# Pollin_NetIO_Clone.net
KiCad netlist of a schematic drawn in EAGLE
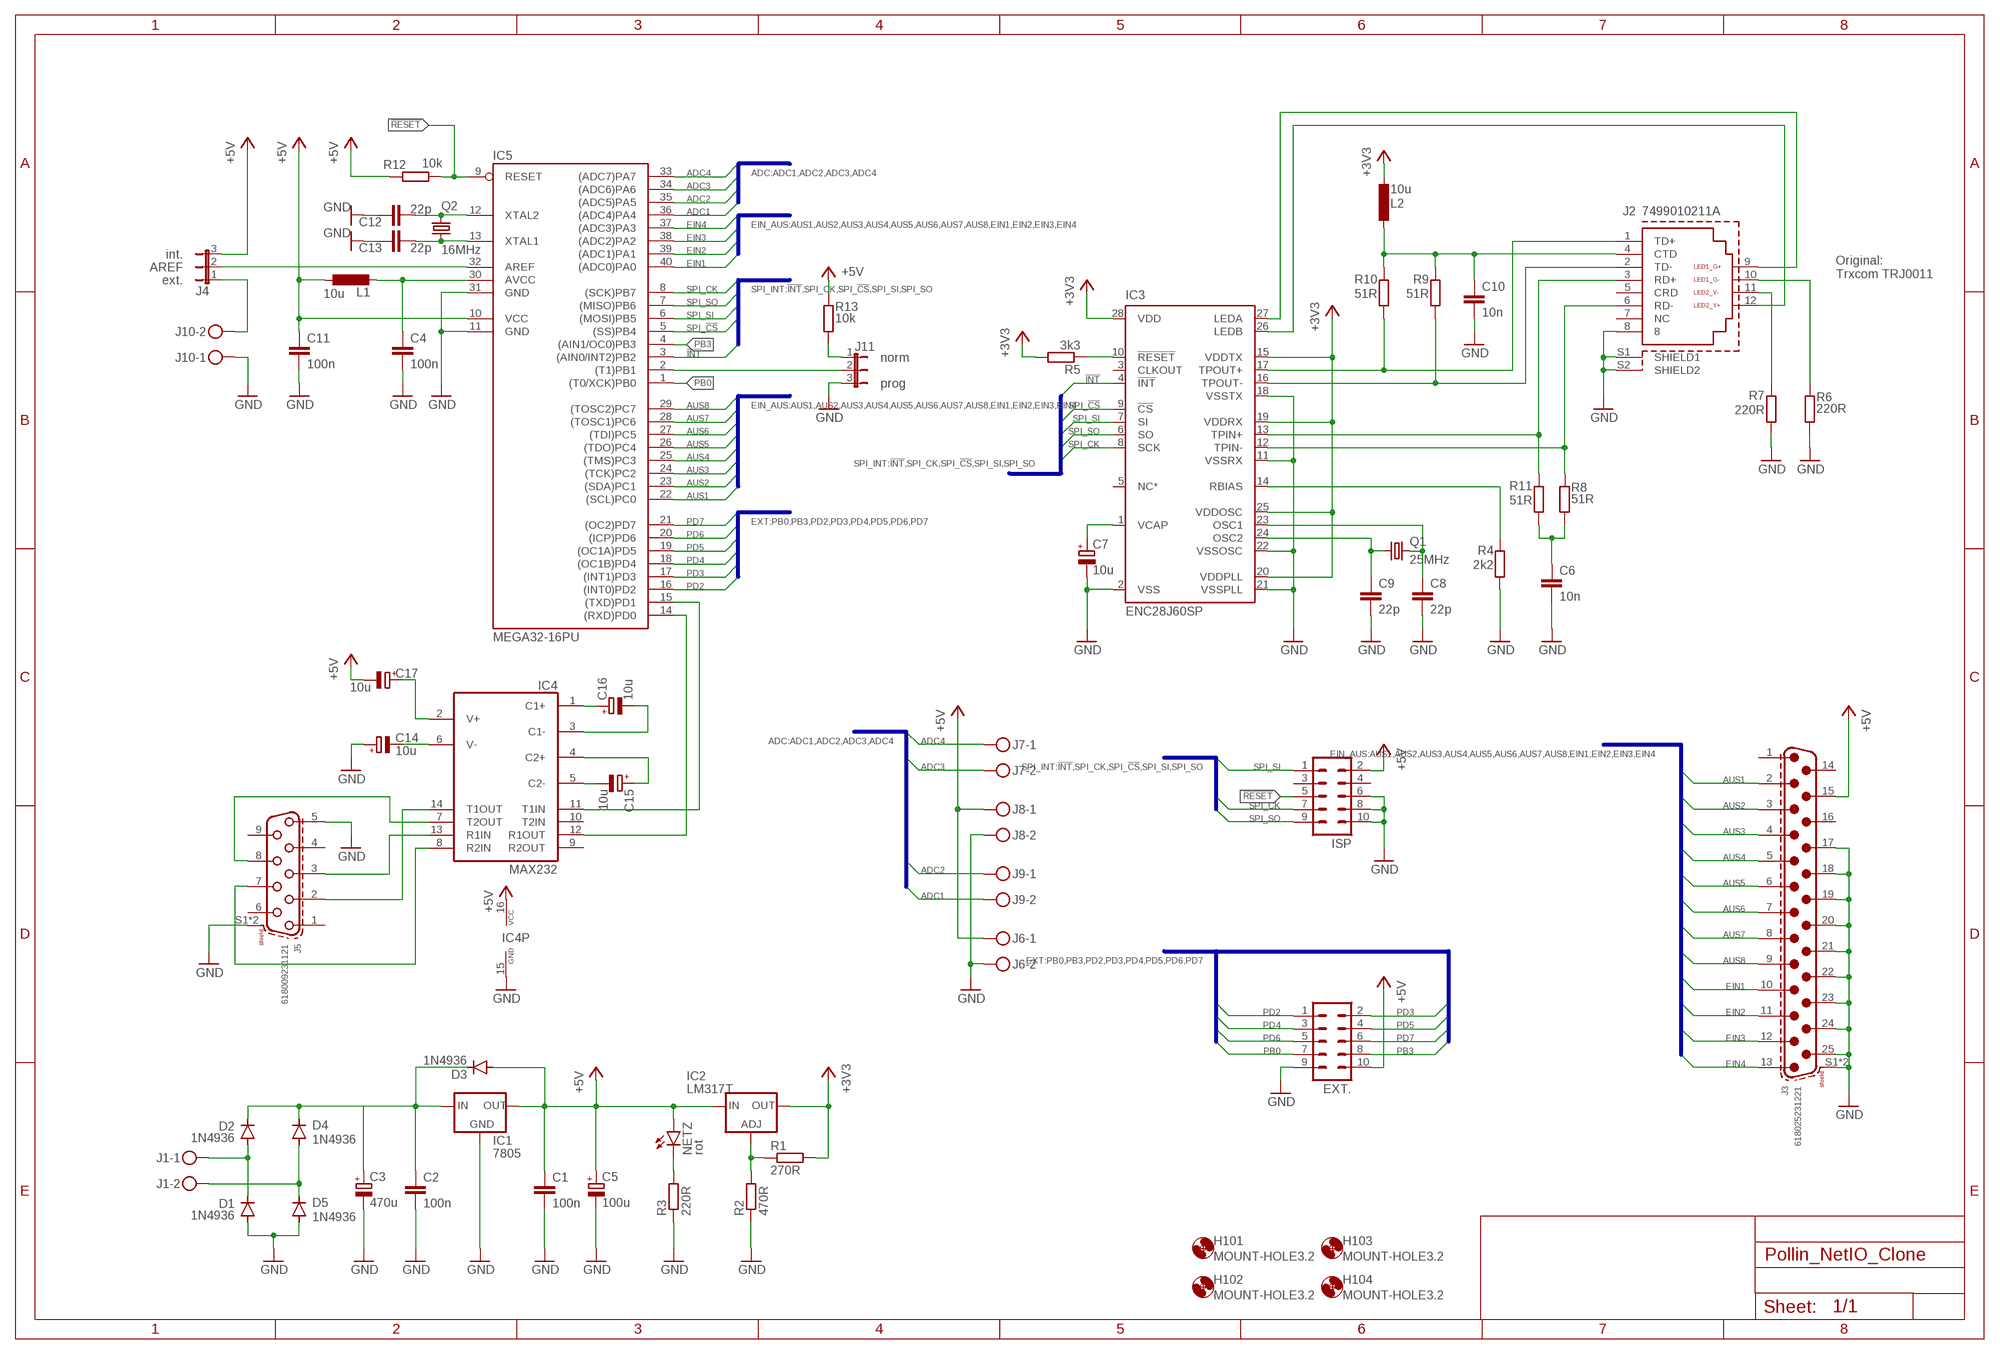
[diagram p0: schematic, sheet 1]

(export (version "E")
  (design (tool "Eeschema 10.0.6"))
  (components
    (comp (ref "C1")
      (value "100n")
      (footprint "eagle-import:C050-025X075")
      (libsource (lib "eagle-import") (part "C-EU050-025X075"))
    )
    (comp (ref "C2")
      (value "100n")
      (footprint "eagle-import:C050-025X075")
      (libsource (lib "eagle-import") (part "C-EU050-025X075"))
    )
    (comp (ref "C3")
      (value "470u")
      (footprint "eagle-import:E5-10,5")
      (libsource (lib "eagle-import") (part "CPOL-EUE5-10.5"))
    )
    (comp (ref "C4")
      (value "100n")
      (footprint "eagle-import:C050-025X075")
      (libsource (lib "eagle-import") (part "C-EU050-025X075"))
    )
    (comp (ref "C5")
      (value "100u")
      (footprint "eagle-import:E5-5")
      (libsource (lib "eagle-import") (part "CPOL-EUE5-5"))
    )
    (comp (ref "C6")
      (value "10n")
      (footprint "eagle-import:C050-025X075")
      (libsource (lib "eagle-import") (part "C-EU050-025X075"))
    )
    (comp (ref "C7")
      (value "10u")
      (footprint "eagle-import:E5-5")
      (libsource (lib "eagle-import") (part "CPOL-EUE5-5"))
    )
    (comp (ref "C8")
      (value "22p")
      (footprint "eagle-import:C050-024X044")
      (libsource (lib "eagle-import") (part "C-EU050-024X044"))
    )
    (comp (ref "C9")
      (value "22p")
      (footprint "eagle-import:C050-024X044")
      (libsource (lib "eagle-import") (part "C-EU050-024X044"))
    )
    (comp (ref "C10")
      (value "10n")
      (footprint "eagle-import:C050-025X075")
      (libsource (lib "eagle-import") (part "C-EU050-025X075"))
    )
    (comp (ref "C11")
      (value "100n")
      (footprint "eagle-import:C050-025X075")
      (libsource (lib "eagle-import") (part "C-EU050-025X075"))
    )
    (comp (ref "C12")
      (value "22p")
      (footprint "eagle-import:C050-024X044")
      (libsource (lib "eagle-import") (part "C-EU050-024X044"))
    )
    (comp (ref "C13")
      (value "22p")
      (footprint "eagle-import:C050-024X044")
      (libsource (lib "eagle-import") (part "C-EU050-024X044"))
    )
    (comp (ref "C14")
      (value "10u")
      (footprint "eagle-import:E5-5")
      (libsource (lib "eagle-import") (part "CPOL-EUE5-5"))
    )
    (comp (ref "C15")
      (value "10u")
      (footprint "eagle-import:E5-5")
      (libsource (lib "eagle-import") (part "CPOL-EUE5-5"))
    )
    (comp (ref "C16")
      (value "10u")
      (footprint "eagle-import:E5-5")
      (libsource (lib "eagle-import") (part "CPOL-EUE5-5"))
    )
    (comp (ref "C17")
      (value "10u")
      (footprint "eagle-import:E5-5")
      (libsource (lib "eagle-import") (part "CPOL-EUE5-5"))
    )
    (comp (ref "D1")
      (value "1N4936")
      (footprint "eagle-import:DO41-10")
      (libsource (lib "eagle-import") (part "1N4933"))
    )
    (comp (ref "D2")
      (value "1N4936")
      (footprint "eagle-import:DO41-10")
      (libsource (lib "eagle-import") (part "1N4933"))
    )
    (comp (ref "D3")
      (value "1N4936")
      (footprint "eagle-import:DO41-10")
      (libsource (lib "eagle-import") (part "1N4933"))
    )
    (comp (ref "D4")
      (value "1N4936")
      (footprint "eagle-import:DO41-10")
      (libsource (lib "eagle-import") (part "1N4933"))
    )
    (comp (ref "D5")
      (value "1N4936")
      (footprint "eagle-import:DO41-10")
      (libsource (lib "eagle-import") (part "1N4933"))
    )
    (comp (ref "EXT.")
      (value "ML10")
      (footprint "eagle-import:ML10")
      (libsource (lib "eagle-import") (part "ML10"))
    )
    (comp (ref "H101")
      (value "MOUNT-HOLE3.2")
      (footprint "eagle-import:3,2")
      (libsource (lib "eagle-import") (part "MOUNT-HOLE3.2"))
    )
    (comp (ref "H102")
      (value "MOUNT-HOLE3.2")
      (footprint "eagle-import:3,2")
      (libsource (lib "eagle-import") (part "MOUNT-HOLE3.2"))
    )
    (comp (ref "H103")
      (value "MOUNT-HOLE3.2")
      (footprint "eagle-import:3,2")
      (libsource (lib "eagle-import") (part "MOUNT-HOLE3.2"))
    )
    (comp (ref "H104")
      (value "MOUNT-HOLE3.2")
      (footprint "eagle-import:3,2")
      (libsource (lib "eagle-import") (part "MOUNT-HOLE3.2"))
    )
    (comp (ref "IC1")
      (value "7805")
      (footprint "eagle-import:78XXS")
      (libsource (lib "eagle-import") (part "78XXS"))
    )
    (comp (ref "IC2")
      (value "LM317T")
      (footprint "eagle-import:317TS")
      (libsource (lib "eagle-import") (part "LM317TS"))
    )
    (comp (ref "IC3")
      (value "ENC28J60SP")
      (footprint "eagle-import:DIL28-3")
      (fields (field (name "MF") "MICROCHIP") (field (name "MPN") "ENC28J60/SP"))
      (libsource (lib "eagle-import") (part "ENC28J60SP"))
    )
    (comp (ref "IC4")
      (value "MAX232")
      (footprint "eagle-import:DIL16")
      (fields (field (name "MF") "MAXIM") (field (name "MPN") "MAX232ACPE+"))
      (libsource (lib "eagle-import") (part "MAX232"))
    )
    (comp (ref "IC5")
      (value "MEGA32-16PU")
      (footprint "eagle-import:DIL40")
      (fields (field (name "MPN") "ATMEGA32-16PU"))
      (libsource (lib "eagle-import") (part "MEGA32-P"))
    )
    (comp (ref "ISP")
      (value "ML10")
      (footprint "eagle-import:ML10")
      (libsource (lib "eagle-import") (part "ML10"))
    )
    (comp (ref "J1")
      (value "MKDSN1,5/2-5,08")
      (footprint "eagle-import:MKDSN1,5_2-5,08")
      (libsource (lib "eagle-import") (part "MKDSN1,5/2-5,08"))
    )
    (comp (ref "J2")
      (value "7499010211A")
      (footprint "eagle-import:7499010211A")
      (libsource (lib "eagle-import") (part "WE-RJ45_7499010211A"))
    )
    (comp (ref "J3")
      (value "618025231221")
      (footprint "eagle-import:618025231221")
      (libsource (lib "eagle-import") (part "6180XX231221_618025231221"))
    )
    (comp (ref "J4")
      (value "JP2E")
      (footprint "eagle-import:JP2")
      (libsource (lib "eagle-import") (part "JP2E"))
    )
    (comp (ref "J5")
      (value "618009231121")
      (footprint "eagle-import:618009231121")
      (libsource (lib "eagle-import") (part "6180XX231121_618009231121"))
    )
    (comp (ref "J6")
      (value "MKDSN1,5/2-5,08")
      (footprint "eagle-import:MKDSN1,5_2-5,08")
      (libsource (lib "eagle-import") (part "MKDSN1,5/2-5,08"))
    )
    (comp (ref "J7")
      (value "MKDSN1,5/2-5,08")
      (footprint "eagle-import:MKDSN1,5_2-5,08")
      (libsource (lib "eagle-import") (part "MKDSN1,5/2-5,08"))
    )
    (comp (ref "J8")
      (value "MKDSN1,5/2-5,08")
      (footprint "eagle-import:MKDSN1,5_2-5,08")
      (libsource (lib "eagle-import") (part "MKDSN1,5/2-5,08"))
    )
    (comp (ref "J9")
      (value "MKDSN1,5/2-5,08")
      (footprint "eagle-import:MKDSN1,5_2-5,08")
      (libsource (lib "eagle-import") (part "MKDSN1,5/2-5,08"))
    )
    (comp (ref "J10")
      (value "MKDSN1,5/2-5,08")
      (footprint "eagle-import:MKDSN1,5_2-5,08")
      (libsource (lib "eagle-import") (part "MKDSN1,5/2-5,08"))
    )
    (comp (ref "J11")
      (value "JP2E")
      (footprint "eagle-import:JP2")
      (libsource (lib "eagle-import") (part "JP2E"))
    )
    (comp (ref "L1")
      (value "10u")
      (footprint "eagle-import:0207_15")
      (libsource (lib "eagle-import") (part "L-EU0207/15"))
    )
    (comp (ref "L2")
      (value "10u")
      (footprint "eagle-import:0207_15")
      (libsource (lib "eagle-import") (part "L-EU0207/15"))
    )
    (comp (ref "NETZ")
      (value "rot")
      (footprint "eagle-import:LED5MM")
      (libsource (lib "eagle-import") (part "LED5MM"))
    )
    (comp (ref "Q1")
      (value "25MHz")
      (footprint "eagle-import:HC49_S")
      (libsource (lib "eagle-import") (part "CRYSTALHC49S"))
    )
    (comp (ref "Q2")
      (value "16MHz")
      (footprint "eagle-import:HC49_S")
      (libsource (lib "eagle-import") (part "CRYSTALHC49S"))
    )
    (comp (ref "R1")
      (value "270R")
      (footprint "eagle-import:0207_10")
      (libsource (lib "eagle-import") (part "R-EU_0207/10"))
    )
    (comp (ref "R2")
      (value "470R")
      (footprint "eagle-import:0207_10")
      (libsource (lib "eagle-import") (part "R-EU_0207/10"))
    )
    (comp (ref "R3")
      (value "220R")
      (footprint "eagle-import:0207_10")
      (libsource (lib "eagle-import") (part "R-EU_0207/10"))
    )
    (comp (ref "R4")
      (value "2k2")
      (footprint "eagle-import:0207_10")
      (libsource (lib "eagle-import") (part "R-EU_0207/10"))
    )
    (comp (ref "R5")
      (value "3k3")
      (footprint "eagle-import:0207_10")
      (libsource (lib "eagle-import") (part "R-EU_0207/10"))
    )
    (comp (ref "R6")
      (value "220R")
      (footprint "eagle-import:0207_10")
      (libsource (lib "eagle-import") (part "R-EU_0207/10"))
    )
    (comp (ref "R7")
      (value "220R")
      (footprint "eagle-import:0207_10")
      (libsource (lib "eagle-import") (part "R-EU_0207/10"))
    )
    (comp (ref "R8")
      (value "51R")
      (footprint "eagle-import:0207_10")
      (libsource (lib "eagle-import") (part "R-EU_0207/10"))
    )
    (comp (ref "R9")
      (value "51R")
      (footprint "eagle-import:0207_10")
      (libsource (lib "eagle-import") (part "R-EU_0207/10"))
    )
    (comp (ref "R10")
      (value "51R")
      (footprint "eagle-import:0207_10")
      (libsource (lib "eagle-import") (part "R-EU_0207/10"))
    )
    (comp (ref "R11")
      (value "51R")
      (footprint "eagle-import:0207_10")
      (libsource (lib "eagle-import") (part "R-EU_0207/10"))
    )
    (comp (ref "R12")
      (value "10k")
      (footprint "eagle-import:0207_10")
      (libsource (lib "eagle-import") (part "R-EU_0207/10"))
    )
    (comp (ref "R13")
      (value "10k")
      (footprint "eagle-import:0207_10")
      (libsource (lib "eagle-import") (part "R-EU_0207/10"))
    )
  )
  (nets
    (net (code "5") (name "+3V3") (class "Default")
      (node (ref "IC2") (pin "2") (pinfunction "OUT_2") (pintype "passive"))
      (node (ref "IC3") (pin "15") (pinfunction "VDDTX_15") (pintype "input"))
      (node (ref "IC3") (pin "19") (pinfunction "VDDRX_19") (pintype "input"))
      (node (ref "IC3") (pin "20") (pinfunction "VDDPLL_20") (pintype "input"))
      (node (ref "IC3") (pin "25") (pinfunction "VDDOSC_25") (pintype "input"))
      (node (ref "IC3") (pin "28") (pinfunction "VDD_28") (pintype "input"))
      (node (ref "L2") (pin "2") (pinfunction "2_2") (pintype "passive"))
      (node (ref "R1") (pin "2") (pinfunction "2_2") (pintype "passive"))
      (node (ref "R5") (pin "2") (pinfunction "2_2") (pintype "passive"))
    )
    (net (code "6") (name "+5V") (class "Default")
      (node (ref "C1") (pin "1") (pinfunction "1_1") (pintype "passive"))
      (node (ref "C11") (pin "1") (pinfunction "1_1") (pintype "passive"))
      (node (ref "C17") (pin "-") (pinfunction "-_-") (pintype "passive"))
      (node (ref "C5") (pin "+") (pinfunction "+_+") (pintype "passive"))
      (node (ref "D3") (pin "A") (pinfunction "A_A") (pintype "passive"))
      (node (ref "EXT.") (pin "10") (pinfunction "10_10") (pintype "passive"))
      (node (ref "IC1") (pin "OUT") (pinfunction "OUT_OUT") (pintype "passive"))
      (node (ref "IC2") (pin "3") (pinfunction "IN_3") (pintype "input"))
      (node (ref "IC4") (pin "16") (pinfunction "VCC_16") (pintype "power_in"))
      (node (ref "IC5") (pin "10") (pinfunction "VCC_10") (pintype "power_in"))
      (node (ref "ISP") (pin "2") (pinfunction "2_2") (pintype "passive"))
      (node (ref "J3") (pin "15") (pinfunction "15_15") (pintype "bidirectional"))
      (node (ref "J4") (pin "3") (pinfunction "3_3") (pintype "passive"))
      (node (ref "J6") (pin "1") (pinfunction "KL_1") (pintype "passive"))
      (node (ref "J8") (pin "1") (pinfunction "KL_1") (pintype "passive"))
      (node (ref "L1") (pin "1") (pinfunction "1_1") (pintype "passive"))
      (node (ref "NETZ") (pin "A") (pinfunction "A_A") (pintype "passive"))
      (node (ref "R12") (pin "1") (pinfunction "1_1") (pintype "passive"))
      (node (ref "R13") (pin "2") (pinfunction "2_2") (pintype "passive"))
    )
    (net (code "7") (name "/ADC1") (class "Default")
      (node (ref "IC5") (pin "36") (pinfunction "(ADC4)PA4_36") (pintype "bidirectional"))
      (node (ref "J9") (pin "2") (pinfunction "KL_2") (pintype "passive"))
    )
    (net (code "8") (name "/ADC2") (class "Default")
      (node (ref "IC5") (pin "35") (pinfunction "(ADC5)PA5_35") (pintype "bidirectional"))
      (node (ref "J9") (pin "1") (pinfunction "KL_1") (pintype "passive"))
    )
    (net (code "9") (name "/ADC3") (class "Default")
      (node (ref "IC5") (pin "34") (pinfunction "(ADC6)PA6_34") (pintype "bidirectional"))
      (node (ref "J7") (pin "2") (pinfunction "KL_2") (pintype "passive"))
    )
    (net (code "10") (name "/ADC4") (class "Default")
      (node (ref "IC5") (pin "33") (pinfunction "(ADC7)PA7_33") (pintype "bidirectional"))
      (node (ref "J7") (pin "1") (pinfunction "KL_1") (pintype "passive"))
    )
    (net (code "11") (name "/AUS1") (class "Default")
      (node (ref "IC5") (pin "22") (pinfunction "(SCL)PC0_22") (pintype "bidirectional"))
      (node (ref "J3") (pin "2") (pinfunction "2_2") (pintype "bidirectional"))
    )
    (net (code "12") (name "/AUS2") (class "Default")
      (node (ref "IC5") (pin "23") (pinfunction "(SDA)PC1_23") (pintype "bidirectional"))
      (node (ref "J3") (pin "3") (pinfunction "3_3") (pintype "bidirectional"))
    )
    (net (code "13") (name "/AUS3") (class "Default")
      (node (ref "IC5") (pin "24") (pinfunction "(TCK)PC2_24") (pintype "bidirectional"))
      (node (ref "J3") (pin "4") (pinfunction "4_4") (pintype "bidirectional"))
    )
    (net (code "14") (name "/AUS4") (class "Default")
      (node (ref "IC5") (pin "25") (pinfunction "(TMS)PC3_25") (pintype "bidirectional"))
      (node (ref "J3") (pin "5") (pinfunction "5_5") (pintype "bidirectional"))
    )
    (net (code "15") (name "/AUS5") (class "Default")
      (node (ref "IC5") (pin "26") (pinfunction "(TDO)PC4_26") (pintype "bidirectional"))
      (node (ref "J3") (pin "6") (pinfunction "6_6") (pintype "bidirectional"))
    )
    (net (code "16") (name "/AUS6") (class "Default")
      (node (ref "IC5") (pin "27") (pinfunction "(TDI)PC5_27") (pintype "bidirectional"))
      (node (ref "J3") (pin "7") (pinfunction "7_7") (pintype "bidirectional"))
    )
    (net (code "17") (name "/AUS7") (class "Default")
      (node (ref "IC5") (pin "28") (pinfunction "(TOSC1)PC6_28") (pintype "bidirectional"))
      (node (ref "J3") (pin "8") (pinfunction "8_8") (pintype "bidirectional"))
    )
    (net (code "18") (name "/AUS8") (class "Default")
      (node (ref "IC5") (pin "29") (pinfunction "(TOSC2)PC7_29") (pintype "bidirectional"))
      (node (ref "J3") (pin "9") (pinfunction "9_9") (pintype "bidirectional"))
    )
    (net (code "19") (name "/EIN1") (class "Default")
      (node (ref "IC5") (pin "40") (pinfunction "(ADC0)PA0_40") (pintype "bidirectional"))
      (node (ref "J3") (pin "10") (pinfunction "10_10") (pintype "bidirectional"))
    )
    (net (code "20") (name "/EIN2") (class "Default")
      (node (ref "IC5") (pin "39") (pinfunction "(ADC1)PA1_39") (pintype "bidirectional"))
      (node (ref "J3") (pin "11") (pinfunction "11_11") (pintype "bidirectional"))
    )
    (net (code "21") (name "/EIN3") (class "Default")
      (node (ref "IC5") (pin "38") (pinfunction "(ADC2)PA2_38") (pintype "bidirectional"))
      (node (ref "J3") (pin "12") (pinfunction "12_12") (pintype "bidirectional"))
    )
    (net (code "22") (name "/EIN4") (class "Default")
      (node (ref "IC5") (pin "37") (pinfunction "(ADC3)PA3_37") (pintype "bidirectional"))
      (node (ref "J3") (pin "13") (pinfunction "13_13") (pintype "bidirectional"))
    )
    (net (code "23") (name "/PD2") (class "Default")
      (node (ref "EXT.") (pin "1") (pinfunction "1_1") (pintype "passive"))
      (node (ref "IC5") (pin "16") (pinfunction "(INT0)PD2_16") (pintype "bidirectional"))
    )
    (net (code "24") (name "/PD3") (class "Default")
      (node (ref "EXT.") (pin "2") (pinfunction "2_2") (pintype "passive"))
      (node (ref "IC5") (pin "17") (pinfunction "(INT1)PD3_17") (pintype "bidirectional"))
    )
    (net (code "25") (name "/PD4") (class "Default")
      (node (ref "EXT.") (pin "3") (pinfunction "3_3") (pintype "passive"))
      (node (ref "IC5") (pin "18") (pinfunction "(OC1B)PD4_18") (pintype "bidirectional"))
    )
    (net (code "26") (name "/PD5") (class "Default")
      (node (ref "EXT.") (pin "4") (pinfunction "4_4") (pintype "passive"))
      (node (ref "IC5") (pin "19") (pinfunction "(OC1A)PD5_19") (pintype "bidirectional"))
    )
    (net (code "27") (name "/PD6") (class "Default")
      (node (ref "EXT.") (pin "5") (pinfunction "5_5") (pintype "passive"))
      (node (ref "IC5") (pin "20") (pinfunction "(ICP)PD6_20") (pintype "bidirectional"))
    )
    (net (code "28") (name "/PD7") (class "Default")
      (node (ref "EXT.") (pin "6") (pinfunction "6_6") (pintype "passive"))
      (node (ref "IC5") (pin "21") (pinfunction "(OC2)PD7_21") (pintype "bidirectional"))
    )
    (net (code "29") (name "/SPI_CK") (class "Default")
      (node (ref "IC3") (pin "8") (pinfunction "SCK_8") (pintype "input"))
      (node (ref "IC5") (pin "8") (pinfunction "(SCK)PB7_8") (pintype "bidirectional"))
      (node (ref "ISP") (pin "7") (pinfunction "7_7") (pintype "passive"))
    )
    (net (code "30") (name "/SPI_SI") (class "Default")
      (node (ref "IC3") (pin "7") (pinfunction "SI_7") (pintype "input"))
      (node (ref "IC5") (pin "6") (pinfunction "(MOSI)PB5_6") (pintype "bidirectional"))
      (node (ref "ISP") (pin "1") (pinfunction "1_1") (pintype "passive"))
    )
    (net (code "31") (name "/SPI_SO") (class "Default")
      (node (ref "IC3") (pin "6") (pinfunction "SO_6") (pintype "output"))
      (node (ref "IC5") (pin "7") (pinfunction "(MISO)PB6_7") (pintype "bidirectional"))
      (node (ref "ISP") (pin "9") (pinfunction "9_9") (pintype "passive"))
    )
    (net (code "32") (name "/SPI_~{CS}") (class "Default")
      (node (ref "IC3") (pin "9") (pinfunction "~{CS}_9") (pintype "input"))
      (node (ref "IC5") (pin "5") (pinfunction "(SS)PB4_5") (pintype "bidirectional"))
    )
    (net (code "37") (name "/~{INT}") (class "Default")
      (node (ref "IC3") (pin "4") (pinfunction "~{INT}_4") (pintype "output"))
      (node (ref "IC5") (pin "3") (pinfunction "(AIN0/INT2)PB2_3") (pintype "bidirectional"))
    )
    (net (code "38") (name "/~{RESET}") (class "Default")
      (node (ref "IC5") (pin "9") (pinfunction "RESET_9") (pintype "input"))
      (node (ref "ISP") (pin "5") (pinfunction "5_5") (pintype "passive"))
      (node (ref "R12") (pin "2") (pinfunction "2_2") (pintype "passive"))
    )
    (net (code "39") (name "GND") (class "Default")
      (node (ref "C1") (pin "2") (pinfunction "2_2") (pintype "passive"))
      (node (ref "C10") (pin "2") (pinfunction "2_2") (pintype "passive"))
      (node (ref "C11") (pin "2") (pinfunction "2_2") (pintype "passive"))
      (node (ref "C12") (pin "1") (pinfunction "1_1") (pintype "passive"))
      (node (ref "C13") (pin "1") (pinfunction "1_1") (pintype "passive"))
      (node (ref "C14") (pin "+") (pinfunction "+_+") (pintype "passive"))
      (node (ref "C2") (pin "2") (pinfunction "2_2") (pintype "passive"))
      (node (ref "C3") (pin "-") (pinfunction "-_-") (pintype "passive"))
      (node (ref "C4") (pin "2") (pinfunction "2_2") (pintype "passive"))
      (node (ref "C5") (pin "-") (pinfunction "-_-") (pintype "passive"))
      (node (ref "C6") (pin "2") (pinfunction "2_2") (pintype "passive"))
      (node (ref "C7") (pin "-") (pinfunction "-_-") (pintype "passive"))
      (node (ref "C8") (pin "2") (pinfunction "2_2") (pintype "passive"))
      (node (ref "C9") (pin "2") (pinfunction "2_2") (pintype "passive"))
      (node (ref "D1") (pin "A") (pinfunction "A_A") (pintype "passive"))
      (node (ref "D5") (pin "A") (pinfunction "A_A") (pintype "passive"))
      (node (ref "EXT.") (pin "9") (pinfunction "9_9") (pintype "passive"))
      (node (ref "IC1") (pin "GND") (pinfunction "GND_GND") (pintype "input"))
      (node (ref "IC3") (pin "11") (pinfunction "VSSRX_11") (pintype "input"))
      (node (ref "IC3") (pin "18") (pinfunction "VSSTX_18") (pintype "input"))
      (node (ref "IC3") (pin "2") (pinfunction "VSS_2") (pintype "input"))
      (node (ref "IC3") (pin "21") (pinfunction "VSSPLL_21") (pintype "input"))
      (node (ref "IC3") (pin "22") (pinfunction "VSSOSC_22") (pintype "input"))
      (node (ref "IC4") (pin "15") (pinfunction "GND_15") (pintype "power_in"))
      (node (ref "IC5") (pin "11") (pinfunction "GND_11") (pintype "power_in"))
      (node (ref "IC5") (pin "31") (pinfunction "GND_31") (pintype "power_in"))
      (node (ref "ISP") (pin "10") (pinfunction "10_10") (pintype "passive"))
      (node (ref "ISP") (pin "6") (pinfunction "6_6") (pintype "passive"))
      (node (ref "ISP") (pin "8") (pinfunction "8_8") (pintype "passive"))
      (node (ref "J10") (pin "1") (pinfunction "KL_1") (pintype "passive"))
      (node (ref "J11") (pin "3") (pinfunction "3_3") (pintype "passive"))
      (node (ref "J2") (pin "8") (pinfunction "8_8") (pintype "passive"))
      (node (ref "J2") (pin "S1") (pinfunction "SHIELD1_S1") (pintype "passive"))
      (node (ref "J2") (pin "S2") (pinfunction "SHIELD2_S2") (pintype "passive"))
      (node (ref "J3") (pin "17") (pinfunction "17_17") (pintype "bidirectional"))
      (node (ref "J3") (pin "18") (pinfunction "18_18") (pintype "bidirectional"))
      (node (ref "J3") (pin "19") (pinfunction "19_19") (pintype "bidirectional"))
      (node (ref "J3") (pin "20") (pinfunction "20_20") (pintype "bidirectional"))
      (node (ref "J3") (pin "21") (pinfunction "21_21") (pintype "bidirectional"))
      (node (ref "J3") (pin "22") (pinfunction "22_22") (pintype "bidirectional"))
      (node (ref "J3") (pin "23") (pinfunction "23_23") (pintype "bidirectional"))
      (node (ref "J3") (pin "24") (pinfunction "24_24") (pintype "bidirectional"))
      (node (ref "J3") (pin "25") (pinfunction "25_25") (pintype "bidirectional"))
      (node (ref "J3") (pin "S1") (pinfunction "SHIELD_S1") (pintype "bidirectional"))
      (node (ref "J3") (pin "S2") (pinfunction "SHIELD_S2") (pintype "bidirectional"))
      (node (ref "J5") (pin "5") (pinfunction "5_5") (pintype "bidirectional"))
      (node (ref "J5") (pin "S1") (pinfunction "SHIELD_S1") (pintype "bidirectional"))
      (node (ref "J5") (pin "S2") (pinfunction "SHIELD_S2") (pintype "bidirectional"))
      (node (ref "J6") (pin "2") (pinfunction "KL_2") (pintype "passive"))
      (node (ref "J8") (pin "2") (pinfunction "KL_2") (pintype "passive"))
      (node (ref "R2") (pin "1") (pinfunction "1_1") (pintype "passive"))
      (node (ref "R3") (pin "1") (pinfunction "1_1") (pintype "passive"))
      (node (ref "R4") (pin "1") (pinfunction "1_1") (pintype "passive"))
      (node (ref "R6") (pin "1") (pinfunction "1_1") (pintype "passive"))
      (node (ref "R7") (pin "1") (pinfunction "1_1") (pintype "passive"))
    )
    (net (code "40") (name "Net-(C2-Pad1)") (class "Default")
      (node (ref "C2") (pin "1") (pinfunction "1_1") (pintype "passive"))
      (node (ref "C3") (pin "+") (pinfunction "+_+") (pintype "passive"))
      (node (ref "D2") (pin "C") (pinfunction "C_C") (pintype "passive"))
      (node (ref "D3") (pin "C") (pinfunction "C_C") (pintype "passive"))
      (node (ref "D4") (pin "C") (pinfunction "C_C") (pintype "passive"))
      (node (ref "IC1") (pin "IN") (pinfunction "IN_IN") (pintype "input"))
    )
    (net (code "41") (name "Net-(C6-Pad1)") (class "Default")
      (node (ref "C6") (pin "1") (pinfunction "1_1") (pintype "passive"))
      (node (ref "R11") (pin "1") (pinfunction "1_1") (pintype "passive"))
      (node (ref "R8") (pin "1") (pinfunction "1_1") (pintype "passive"))
    )
    (net (code "42") (name "Net-(IC2-ADJ)") (class "Default")
      (node (ref "IC2") (pin "1") (pinfunction "ADJ_1") (pintype "input"))
      (node (ref "R1") (pin "1") (pinfunction "1_1") (pintype "passive"))
      (node (ref "R2") (pin "2") (pinfunction "2_2") (pintype "passive"))
    )
    (net (code "43") (name "Net-(IC3-LEDA)") (class "Default")
      (node (ref "IC3") (pin "27") (pinfunction "LEDA_27") (pintype "output"))
      (node (ref "J2") (pin "9") (pinfunction "LED1_G+_9") (pintype "passive"))
    )
    (net (code "44") (name "Net-(IC3-LEDB)") (class "Default")
      (node (ref "IC3") (pin "26") (pinfunction "LEDB_26") (pintype "output"))
      (node (ref "J2") (pin "12") (pinfunction "LED2_Y+_12") (pintype "passive"))
    )
    (net (code "45") (name "Net-(IC3-OSC1)") (class "Default")
      (node (ref "C8") (pin "1") (pinfunction "1_1") (pintype "passive"))
      (node (ref "IC3") (pin "23") (pinfunction "OSC1_23") (pintype "input"))
      (node (ref "Q1") (pin "1") (pinfunction "1_1") (pintype "passive"))
    )
    (net (code "46") (name "Net-(IC3-OSC2)") (class "Default")
      (node (ref "C9") (pin "1") (pinfunction "1_1") (pintype "passive"))
      (node (ref "IC3") (pin "24") (pinfunction "OSC2_24") (pintype "output"))
      (node (ref "Q1") (pin "2") (pinfunction "2_2") (pintype "passive"))
    )
    (net (code "47") (name "Net-(IC3-RBIAS)") (class "Default")
      (node (ref "IC3") (pin "14") (pinfunction "RBIAS_14") (pintype "input"))
      (node (ref "R4") (pin "2") (pinfunction "2_2") (pintype "passive"))
    )
    (net (code "48") (name "Net-(IC3-TPIN+)") (class "Default")
      (node (ref "IC3") (pin "13") (pinfunction "TPIN+_13") (pintype "input"))
      (node (ref "J2") (pin "3") (pinfunction "RD+_3") (pintype "passive"))
      (node (ref "R11") (pin "2") (pinfunction "2_2") (pintype "passive"))
    )
    (net (code "49") (name "Net-(IC3-TPIN-)") (class "Default")
      (node (ref "IC3") (pin "12") (pinfunction "TPIN-_12") (pintype "input"))
      (node (ref "J2") (pin "6") (pinfunction "RD-_6") (pintype "passive"))
      (node (ref "R8") (pin "2") (pinfunction "2_2") (pintype "passive"))
    )
    (net (code "50") (name "Net-(IC3-TPOUT+)") (class "Default")
      (node (ref "IC3") (pin "17") (pinfunction "TPOUT+_17") (pintype "output"))
      (node (ref "J2") (pin "1") (pinfunction "TD+_1") (pintype "passive"))
      (node (ref "R10") (pin "1") (pinfunction "1_1") (pintype "passive"))
    )
    (net (code "51") (name "Net-(IC3-TPOUT-)") (class "Default")
      (node (ref "IC3") (pin "16") (pinfunction "TPOUT-_16") (pintype "output"))
      (node (ref "J2") (pin "2") (pinfunction "TD-_2") (pintype "passive"))
      (node (ref "R9") (pin "1") (pinfunction "1_1") (pintype "passive"))
    )
    (net (code "52") (name "Net-(IC3-VCAP)") (class "Default")
      (node (ref "C7") (pin "+") (pinfunction "+_+") (pintype "passive"))
      (node (ref "IC3") (pin "1") (pinfunction "VCAP_1") (pintype "input"))
    )
    (net (code "53") (name "Net-(IC3-~{RESET})") (class "Default")
      (node (ref "IC3") (pin "10") (pinfunction "~{RESET}_10") (pintype "input"))
      (node (ref "R5") (pin "1") (pinfunction "1_1") (pintype "passive"))
    )
    (net (code "54") (name "Net-(IC4A-C1+)") (class "Default")
      (node (ref "C16") (pin "+") (pinfunction "+_+") (pintype "passive"))
      (node (ref "IC4") (pin "1") (pinfunction "C1+_1") (pintype "bidirectional"))
    )
    (net (code "55") (name "Net-(IC4A-C1-)") (class "Default")
      (node (ref "C16") (pin "-") (pinfunction "-_-") (pintype "passive"))
      (node (ref "IC4") (pin "3") (pinfunction "C1-_3") (pintype "bidirectional"))
    )
    (net (code "56") (name "Net-(IC4A-C2+)") (class "Default")
      (node (ref "C15") (pin "+") (pinfunction "+_+") (pintype "passive"))
      (node (ref "IC4") (pin "4") (pinfunction "C2+_4") (pintype "bidirectional"))
    )
    (net (code "57") (name "Net-(IC4A-C2-)") (class "Default")
      (node (ref "C15") (pin "-") (pinfunction "-_-") (pintype "passive"))
      (node (ref "IC4") (pin "5") (pinfunction "C2-_5") (pintype "bidirectional"))
    )
    (net (code "58") (name "Net-(IC4A-R1IN)") (class "Default")
      (node (ref "IC4") (pin "13") (pinfunction "R1IN_13") (pintype "input"))
      (node (ref "J5") (pin "3") (pinfunction "3_3") (pintype "bidirectional"))
    )
    (net (code "59") (name "Net-(IC4A-R1OUT)") (class "Default")
      (node (ref "IC4") (pin "12") (pinfunction "R1OUT_12") (pintype "output"))
      (node (ref "IC5") (pin "14") (pinfunction "(RXD)PD0_14") (pintype "bidirectional"))
    )
    (net (code "60") (name "Net-(IC4A-R2IN)") (class "Default")
      (node (ref "IC4") (pin "8") (pinfunction "R2IN_8") (pintype "input"))
      (node (ref "J5") (pin "7") (pinfunction "7_7") (pintype "bidirectional"))
    )
    (net (code "61") (name "Net-(IC4A-T1IN)") (class "Default")
      (node (ref "IC4") (pin "11") (pinfunction "T1IN_11") (pintype "input"))
      (node (ref "IC5") (pin "15") (pinfunction "(TXD)PD1_15") (pintype "bidirectional"))
    )
    (net (code "62") (name "Net-(IC4A-T1OUT)") (class "Default")
      (node (ref "IC4") (pin "14") (pinfunction "T1OUT_14") (pintype "output"))
      (node (ref "J5") (pin "2") (pinfunction "2_2") (pintype "bidirectional"))
    )
    (net (code "63") (name "Net-(IC4A-T2OUT)") (class "Default")
      (node (ref "IC4") (pin "7") (pinfunction "T2OUT_7") (pintype "output"))
      (node (ref "J5") (pin "8") (pinfunction "8_8") (pintype "bidirectional"))
    )
    (net (code "64") (name "Net-(IC4A-V+)") (class "Default")
      (node (ref "C17") (pin "+") (pinfunction "+_+") (pintype "passive"))
      (node (ref "IC4") (pin "2") (pinfunction "V+_2") (pintype "bidirectional"))
    )
    (net (code "65") (name "Net-(IC4A-V-)") (class "Default")
      (node (ref "C14") (pin "-") (pinfunction "-_-") (pintype "passive"))
      (node (ref "IC4") (pin "6") (pinfunction "V-_6") (pintype "bidirectional"))
    )
    (net (code "66") (name "Net-(IC5-(T1)PB1)") (class "Default")
      (node (ref "IC5") (pin "2") (pinfunction "(T1)PB1_2") (pintype "bidirectional"))
      (node (ref "J11") (pin "2") (pinfunction "2_2") (pintype "passive"))
    )
    (net (code "67") (name "Net-(IC5-AREF)") (class "Default")
      (node (ref "IC5") (pin "32") (pinfunction "AREF_32") (pintype "passive"))
      (node (ref "J4") (pin "2") (pinfunction "2_2") (pintype "passive"))
    )
    (net (code "68") (name "Net-(IC5-AVCC)") (class "Default")
      (node (ref "C4") (pin "1") (pinfunction "1_1") (pintype "passive"))
      (node (ref "IC5") (pin "30") (pinfunction "AVCC_30") (pintype "power_in"))
      (node (ref "L1") (pin "2") (pinfunction "2_2") (pintype "passive"))
    )
    (net (code "69") (name "Net-(IC5-XTAL1)") (class "Default")
      (node (ref "C13") (pin "2") (pinfunction "2_2") (pintype "passive"))
      (node (ref "IC5") (pin "13") (pinfunction "XTAL1_13") (pintype "bidirectional"))
      (node (ref "Q2") (pin "1") (pinfunction "1_1") (pintype "passive"))
    )
    (net (code "70") (name "Net-(IC5-XTAL2)") (class "Default")
      (node (ref "C12") (pin "2") (pinfunction "2_2") (pintype "passive"))
      (node (ref "IC5") (pin "12") (pinfunction "XTAL2_12") (pintype "bidirectional"))
      (node (ref "Q2") (pin "2") (pinfunction "2_2") (pintype "passive"))
    )
    (net (code "71") (name "Net-(J1A-KL)") (class "Default")
      (node (ref "D1") (pin "C") (pinfunction "C_C") (pintype "passive"))
      (node (ref "D2") (pin "A") (pinfunction "A_A") (pintype "passive"))
      (node (ref "J1") (pin "1") (pinfunction "KL_1") (pintype "passive"))
    )
    (net (code "72") (name "Net-(J1B-KL)") (class "Default")
      (node (ref "D4") (pin "A") (pinfunction "A_A") (pintype "passive"))
      (node (ref "D5") (pin "C") (pinfunction "C_C") (pintype "passive"))
      (node (ref "J1") (pin "2") (pinfunction "KL_2") (pintype "passive"))
    )
    (net (code "73") (name "Net-(J2-CTD)") (class "Default")
      (node (ref "C10") (pin "1") (pinfunction "1_1") (pintype "passive"))
      (node (ref "J2") (pin "4") (pinfunction "CTD_4") (pintype "passive"))
      (node (ref "L2") (pin "1") (pinfunction "1_1") (pintype "passive"))
      (node (ref "R10") (pin "2") (pinfunction "2_2") (pintype "passive"))
      (node (ref "R9") (pin "2") (pinfunction "2_2") (pintype "passive"))
    )
    (net (code "74") (name "Net-(J2-LED1_G-)") (class "Default")
      (node (ref "J2") (pin "10") (pinfunction "LED1_G-_10") (pintype "passive"))
      (node (ref "R6") (pin "2") (pinfunction "2_2") (pintype "passive"))
    )
    (net (code "75") (name "Net-(J2-LED2_Y-)") (class "Default")
      (node (ref "J2") (pin "11") (pinfunction "LED2_Y-_11") (pintype "passive"))
      (node (ref "R7") (pin "2") (pinfunction "2_2") (pintype "passive"))
    )
    (net (code "76") (name "Net-(J10B-KL)") (class "Default")
      (node (ref "J10") (pin "2") (pinfunction "KL_2") (pintype "passive"))
      (node (ref "J4") (pin "1") (pinfunction "1_1") (pintype "passive"))
    )
    (net (code "77") (name "Net-(J11-Pad1)") (class "Default")
      (node (ref "J11") (pin "1") (pinfunction "1_1") (pintype "passive"))
      (node (ref "R13") (pin "1") (pinfunction "1_1") (pintype "passive"))
    )
    (net (code "78") (name "Net-(NETZ-C)") (class "Default")
      (node (ref "NETZ") (pin "K") (pinfunction "C_K") (pintype "passive"))
      (node (ref "R3") (pin "2") (pinfunction "2_2") (pintype "passive"))
    )
    (net (code "79") (name "PB0") (class "Default")
      (node (ref "EXT.") (pin "7") (pinfunction "7_7") (pintype "passive"))
      (node (ref "IC5") (pin "1") (pinfunction "(T0/XCK)PB0_1") (pintype "bidirectional"))
    )
    (net (code "80") (name "PB3") (class "Default")
      (node (ref "EXT.") (pin "8") (pinfunction "8_8") (pintype "passive"))
      (node (ref "IC5") (pin "4") (pinfunction "(AIN1/OC0)PB3_4") (pintype "bidirectional"))
    )
    (net (code "81") (name "unconnected-(IC3-CLKOUT-Pad3)") (class "Default")
      (node (ref "IC3") (pin "3") (pinfunction "CLKOUT_3") (pintype "output"))
    )
    (net (code "82") (name "unconnected-(IC3-NC*-Pad5)") (class "Default")
      (node (ref "IC3") (pin "5") (pinfunction "NC*_5") (pintype "output"))
    )
    (net (code "83") (name "unconnected-(IC4A-R2OUT-Pad9)") (class "Default")
      (node (ref "IC4") (pin "9") (pinfunction "R2OUT_9") (pintype "output"))
    )
    (net (code "84") (name "unconnected-(IC4A-T2IN-Pad10)") (class "Default")
      (node (ref "IC4") (pin "10") (pinfunction "T2IN_10") (pintype "input"))
    )
    (net (code "85") (name "unconnected-(ISP-Pad3)") (class "Default")
      (node (ref "ISP") (pin "3") (pinfunction "3_3") (pintype "passive"))
    )
    (net (code "86") (name "unconnected-(ISP-Pad4)") (class "Default")
      (node (ref "ISP") (pin "4") (pinfunction "4_4") (pintype "passive"))
    )
    (net (code "87") (name "unconnected-(J2-CRD-Pad5)") (class "Default")
      (node (ref "J2") (pin "5") (pinfunction "CRD_5") (pintype "passive"))
    )
    (net (code "88") (name "unconnected-(J2-NC-Pad7)") (class "Default")
      (node (ref "J2") (pin "7") (pinfunction "NC_7") (pintype "passive"))
    )
    (net (code "89") (name "unconnected-(J3-Pad1)") (class "Default")
      (node (ref "J3") (pin "1") (pinfunction "1_1") (pintype "bidirectional"))
    )
    (net (code "90") (name "unconnected-(J3-Pad14)") (class "Default")
      (node (ref "J3") (pin "14") (pinfunction "14_14") (pintype "bidirectional"))
    )
    (net (code "91") (name "unconnected-(J3-Pad16)") (class "Default")
      (node (ref "J3") (pin "16") (pinfunction "16_16") (pintype "bidirectional"))
    )
    (net (code "92") (name "unconnected-(J5-Pad1)") (class "Default")
      (node (ref "J5") (pin "1") (pinfunction "1_1") (pintype "bidirectional"))
    )
    (net (code "93") (name "unconnected-(J5-Pad4)") (class "Default")
      (node (ref "J5") (pin "4") (pinfunction "4_4") (pintype "bidirectional"))
    )
    (net (code "94") (name "unconnected-(J5-Pad6)") (class "Default")
      (node (ref "J5") (pin "6") (pinfunction "6_6") (pintype "bidirectional"))
    )
    (net (code "95") (name "unconnected-(J5-Pad9)") (class "Default")
      (node (ref "J5") (pin "9") (pinfunction "9_9") (pintype "bidirectional"))
    )
  )
)
